# MeArm-v5.net
KiCad netlist of a schematic drawn in EAGLE
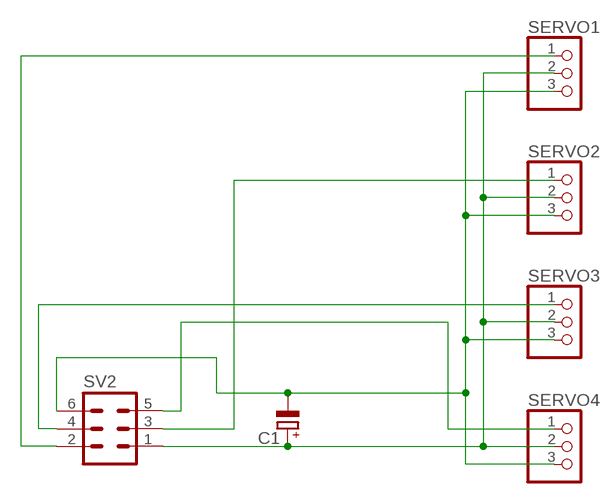
[diagram p0: schematic, sheet 1]

(export (version "E")
  (design (tool "Eeschema 10.0.6"))
  (components
    (comp (ref "C1")
      (value "CPOL-EUE2.5-6")
      (footprint "eagle-import:E2,5-6")
      (libsource (lib "eagle-import") (part "CPOL-EUE2.5-6"))
    )
    (comp (ref "SERVO1")
      (value "PINHD-1X3")
      (footprint "eagle-import:1X03")
      (libsource (lib "eagle-import") (part "PINHD-1X3"))
    )
    (comp (ref "SERVO2")
      (value "PINHD-1X3")
      (footprint "eagle-import:1X03")
      (libsource (lib "eagle-import") (part "PINHD-1X3"))
    )
    (comp (ref "SERVO3")
      (value "PINHD-1X3")
      (footprint "eagle-import:1X03")
      (libsource (lib "eagle-import") (part "PINHD-1X3"))
    )
    (comp (ref "SERVO4")
      (value "PINHD-1X3")
      (footprint "eagle-import:1X03")
      (libsource (lib "eagle-import") (part "PINHD-1X3"))
    )
    (comp (ref "SV2")
      (value "ML6")
      (footprint "eagle-import:ML6")
      (libsource (lib "eagle-import") (part "ML6"))
    )
  )
  (nets
    (net (code "1") (name "Net-(C1-Pad+)") (class "Default")
      (node (ref "C1") (pin "+") (pinfunction "+_+") (pintype "passive"))
      (node (ref "SERVO1") (pin "2") (pinfunction "2_2") (pintype "passive"))
      (node (ref "SERVO2") (pin "2") (pinfunction "2_2") (pintype "passive"))
      (node (ref "SERVO3") (pin "2") (pinfunction "2_2") (pintype "passive"))
      (node (ref "SERVO4") (pin "2") (pinfunction "2_2") (pintype "passive"))
      (node (ref "SV2") (pin "1") (pinfunction "1_1") (pintype "passive"))
    )
    (net (code "2") (name "Net-(C1-Pad-)") (class "Default")
      (node (ref "C1") (pin "-") (pinfunction "-_-") (pintype "passive"))
      (node (ref "SERVO1") (pin "3") (pinfunction "3_3") (pintype "passive"))
      (node (ref "SERVO2") (pin "3") (pinfunction "3_3") (pintype "passive"))
      (node (ref "SERVO3") (pin "3") (pinfunction "3_3") (pintype "passive"))
      (node (ref "SERVO4") (pin "3") (pinfunction "3_3") (pintype "passive"))
      (node (ref "SV2") (pin "6") (pinfunction "6_6") (pintype "passive"))
    )
    (net (code "3") (name "Net-(SERVO1-Pad1)") (class "Default")
      (node (ref "SERVO1") (pin "1") (pinfunction "1_1") (pintype "passive"))
      (node (ref "SV2") (pin "2") (pinfunction "2_2") (pintype "passive"))
    )
    (net (code "4") (name "Net-(SERVO2-Pad1)") (class "Default")
      (node (ref "SERVO2") (pin "1") (pinfunction "1_1") (pintype "passive"))
      (node (ref "SV2") (pin "3") (pinfunction "3_3") (pintype "passive"))
    )
    (net (code "5") (name "Net-(SERVO3-Pad1)") (class "Default")
      (node (ref "SERVO3") (pin "1") (pinfunction "1_1") (pintype "passive"))
      (node (ref "SV2") (pin "4") (pinfunction "4_4") (pintype "passive"))
    )
    (net (code "6") (name "Net-(SERVO4-Pad1)") (class "Default")
      (node (ref "SERVO4") (pin "1") (pinfunction "1_1") (pintype "passive"))
      (node (ref "SV2") (pin "5") (pinfunction "5_5") (pintype "passive"))
    )
  )
)
